# CATS-Vega-Pyro_Enable.net
KiCad netlist of a schematic drawn in Altium Designer
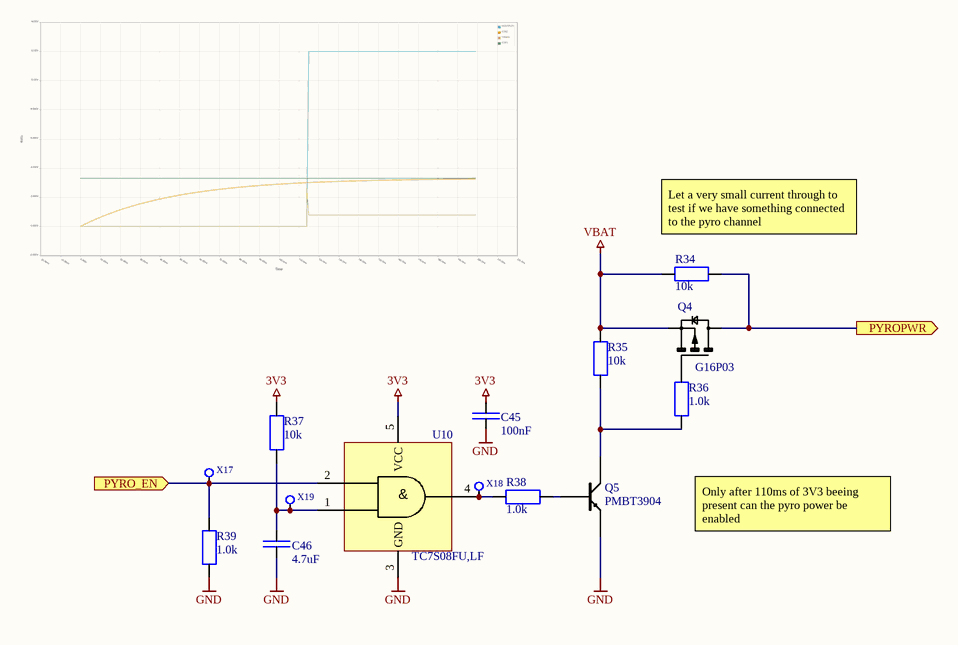
[diagram p0: CATS-Vega-Pyro_Enable.SchDoc]

(export (version "E")
  (design (tool "Eeschema 10.0.6"))
  (components
    (comp (ref "C45")
      (value "100nF")
      (footprint "SMD Keramikkondensator 0603")
      (description "SMD Ceramic Capacitor E6")
      (libsource (lib "CATS-EUROC") (part "E6 - 100nF"))
    )
    (comp (ref "C46")
      (value "4.7uF")
      (footprint "SMD Keramikkondensator 0603")
      (description "SMD Ceramic Capacitor E6")
      (libsource (lib "CATS-EUROC") (part "E6 - 4.7uF"))
    )
    (comp (ref "Q4")
      (value "G16P03")
      (footprint "SMD MOSFET DFN 3x3 EP")
      (description "30V 16A 35W")
      (libsource (lib "Electronic Switches") (part "G16P03"))
    )
    (comp (ref "Q5")
      (value "PMBT3904")
      (footprint "SMD Transistor SOT-23")
      (description "40 V, 200 mA NPN switching transisto")
      (libsource (lib "Electronic Switches") (part "PMBT3904"))
    )
    (comp (ref "R34")
      (value "10k")
      (footprint "SMD Widerstand 0603")
      (description "SMD Chip Resistor E24")
      (libsource (lib "") (part "E24 - 10k_1"))
    )
    (comp (ref "R35")
      (value "10k")
      (footprint "SMD Widerstand 0603")
      (description "SMD Chip Resistor E24")
      (libsource (lib "CATS-EUROC") (part "E24 - 10k"))
    )
    (comp (ref "R36")
      (value "1.0k")
      (footprint "SMD Widerstand 0603")
      (description "SMD Chip Resistor E24")
      (libsource (lib "") (part "E24 - 1.0k_1"))
    )
    (comp (ref "R37")
      (value "10k")
      (footprint "SMD Widerstand 0603")
      (description "SMD Chip Resistor E24")
      (libsource (lib "CATS-EUROC") (part "E24 - 10k"))
    )
    (comp (ref "R38")
      (value "1.0k")
      (footprint "SMD Widerstand 0603")
      (description "SMD Chip Resistor E24")
      (libsource (lib "CATS-EUROC") (part "E24 - 1.0k"))
    )
    (comp (ref "R39")
      (value "1.0k")
      (footprint "SMD Widerstand 0603")
      (description "SMD Chip Resistor E24")
      (libsource (lib "") (part "E24 - 1.0k_1"))
    )
    (comp (ref "U10")
      (value "TC7S08FU,LF")
      (footprint "SMD IC SSOP5-P-0.65A (SOT353-1)")
      (description "AND Gate SSOP5-P-0.65A")
      (libsource (lib "Digital") (part "TC7S08FU,LF"))
    )
    (comp (ref "X17")
      (value "-")
      (footprint "SMD Test point 0.8mm")
      (description "Test Point SMD")
      (libsource (lib "Connectors") (part "SMD Test point"))
    )
    (comp (ref "X18")
      (value "-")
      (footprint "SMD Test point 0.8mm")
      (description "Test Point SMD")
      (libsource (lib "Connectors") (part "SMD Test point"))
    )
    (comp (ref "X19")
      (value "-")
      (footprint "SMD Test point 0.8mm")
      (description "Test Point SMD")
      (libsource (lib "Connectors") (part "SMD Test point"))
    )
  )
  (nets
    (net (code "1") (name "/PYROPWR") (class "Default")
      (node (ref "Q4") (pin "D") (pinfunction "D_D") (pintype "passive"))
      (node (ref "R34") (pin "1") (pinfunction "1_1") (pintype "passive"))
    )
    (net (code "2") (name "/PYRO_EN") (class "Default")
      (node (ref "R39") (pin "2") (pinfunction "2_2") (pintype "passive"))
      (node (ref "U10") (pin "2") (pinfunction "IN_2") (pintype "passive"))
      (node (ref "X17") (pin "1") (pinfunction "1_1") (pintype "passive"))
    )
    (net (code "3") (name "3V3") (class "Default")
      (node (ref "C45") (pin "2") (pinfunction "2_2") (pintype "passive"))
      (node (ref "R37") (pin "2") (pinfunction "2_2") (pintype "passive"))
      (node (ref "U10") (pin "5") (pinfunction "VCC_5") (pintype "passive"))
    )
    (net (code "4") (name "GND") (class "Default")
      (node (ref "C45") (pin "1") (pinfunction "1_1") (pintype "passive"))
      (node (ref "C46") (pin "1") (pinfunction "1_1") (pintype "passive"))
      (node (ref "Q5") (pin "E") (pintype "passive"))
      (node (ref "R39") (pin "1") (pinfunction "1_1") (pintype "passive"))
      (node (ref "U10") (pin "3") (pinfunction "GND_3") (pintype "passive"))
    )
    (net (code "5") (name "Net-(C46-Pad2)") (class "Default")
      (node (ref "C46") (pin "2") (pinfunction "2_2") (pintype "passive"))
      (node (ref "R37") (pin "1") (pinfunction "1_1") (pintype "passive"))
      (node (ref "U10") (pin "1") (pinfunction "IN_1") (pintype "passive"))
      (node (ref "X19") (pin "1") (pinfunction "1_1") (pintype "passive"))
    )
    (net (code "6") (name "Net-(Q4-PadG)") (class "Default")
      (node (ref "Q4") (pin "G") (pinfunction "G_G") (pintype "passive"))
      (node (ref "R36") (pin "2") (pinfunction "2_2") (pintype "passive"))
    )
    (net (code "7") (name "Net-(Q5-PadB)") (class "Default")
      (node (ref "Q5") (pin "B") (pintype "passive"))
      (node (ref "R38") (pin "1") (pinfunction "1_1") (pintype "passive"))
    )
    (net (code "8") (name "Net-(Q5-PadC)") (class "Default")
      (node (ref "Q5") (pin "C") (pintype "passive"))
      (node (ref "R35") (pin "1") (pinfunction "1_1") (pintype "passive"))
      (node (ref "R36") (pin "1") (pinfunction "1_1") (pintype "passive"))
    )
    (net (code "9") (name "Net-(U10-OUT)") (class "Default")
      (node (ref "R38") (pin "2") (pinfunction "2_2") (pintype "passive"))
      (node (ref "U10") (pin "4") (pinfunction "OUT_4") (pintype "passive"))
      (node (ref "X18") (pin "1") (pinfunction "1_1") (pintype "passive"))
    )
    (net (code "10") (name "VBAT") (class "Default")
      (node (ref "Q4") (pin "S") (pinfunction "S_S") (pintype "passive"))
      (node (ref "R34") (pin "2") (pinfunction "2_2") (pintype "passive"))
      (node (ref "R35") (pin "2") (pinfunction "2_2") (pintype "passive"))
    )
  )
)
